# Mechanical.net
KiCad netlist of a schematic drawn in Altium Designer
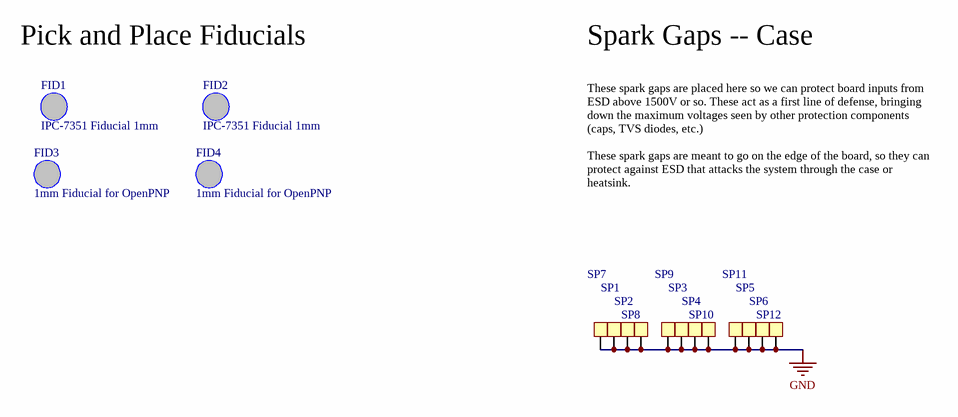
[diagram p0: Mechanical.SchDoc]

(export (version "E")
  (design (tool "Eeschema 10.0.6"))
  (components
    (comp (ref "FID1")
      (value "IPC-7351 Fiducial 1mm")
      (footprint "FIDUCIAL_1.5")
      (libsource (lib "Mechanical") (part "FIDUCIAL_1.5"))
    )
    (comp (ref "FID2")
      (value "IPC-7351 Fiducial 1mm")
      (footprint "FIDUCIAL_1.5")
      (libsource (lib "Mechanical") (part "FIDUCIAL_1.5"))
    )
    (comp (ref "FID3")
      (value "1mm Fiducial for OpenPNP")
      (footprint "FIDUCIAL-NEW")
      (libsource (lib "Mechanical") (part "FIDUCIAL_NEW"))
    )
    (comp (ref "FID4")
      (value "1mm Fiducial for OpenPNP")
      (footprint "FIDUCIAL-NEW")
      (libsource (lib "Mechanical") (part "FIDUCIAL_NEW"))
    )
    (comp (ref "SP1")
      (value "Spark Gap")
      (footprint "SparkGap")
      (description "Open square pad for spark gapping")
      (libsource (lib "PCBFeatures") (part "Spark Gap"))
    )
    (comp (ref "SP2")
      (value "Spark Gap")
      (footprint "SparkGap")
      (description "Open square pad for spark gapping")
      (libsource (lib "PCBFeatures") (part "Spark Gap"))
    )
    (comp (ref "SP3")
      (value "Spark Gap")
      (footprint "SparkGap")
      (description "Open square pad for spark gapping")
      (libsource (lib "PCBFeatures") (part "Spark Gap"))
    )
    (comp (ref "SP4")
      (value "Spark Gap")
      (footprint "SparkGap")
      (description "Open square pad for spark gapping")
      (libsource (lib "PCBFeatures") (part "Spark Gap"))
    )
    (comp (ref "SP5")
      (value "Spark Gap")
      (footprint "SparkGap")
      (description "Open square pad for spark gapping")
      (libsource (lib "PCBFeatures") (part "Spark Gap"))
    )
    (comp (ref "SP6")
      (value "Spark Gap")
      (footprint "SparkGap")
      (description "Open square pad for spark gapping")
      (libsource (lib "PCBFeatures") (part "Spark Gap"))
    )
    (comp (ref "SP7")
      (value "Spark Gap")
      (footprint "SparkGap")
      (description "Open square pad for spark gapping")
      (libsource (lib "PCBFeatures") (part "Spark Gap"))
    )
    (comp (ref "SP8")
      (value "Spark Gap")
      (footprint "SparkGap")
      (description "Open square pad for spark gapping")
      (libsource (lib "PCBFeatures") (part "Spark Gap"))
    )
    (comp (ref "SP9")
      (value "Spark Gap")
      (footprint "SparkGap")
      (description "Open square pad for spark gapping")
      (libsource (lib "PCBFeatures") (part "Spark Gap"))
    )
    (comp (ref "SP10")
      (value "Spark Gap")
      (footprint "SparkGap")
      (description "Open square pad for spark gapping")
      (libsource (lib "PCBFeatures") (part "Spark Gap"))
    )
    (comp (ref "SP11")
      (value "Spark Gap")
      (footprint "SparkGap")
      (description "Open square pad for spark gapping")
      (libsource (lib "PCBFeatures") (part "Spark Gap"))
    )
    (comp (ref "SP12")
      (value "Spark Gap")
      (footprint "SparkGap")
      (description "Open square pad for spark gapping")
      (libsource (lib "PCBFeatures") (part "Spark Gap"))
    )
  )
  (nets
    (net (code "1") (name "GND") (class "Default")
      (node (ref "SP1") (pin "1") (pinfunction "1_1") (pintype "passive"))
      (node (ref "SP10") (pin "1") (pinfunction "1_1") (pintype "passive"))
      (node (ref "SP11") (pin "1") (pinfunction "1_1") (pintype "passive"))
      (node (ref "SP12") (pin "1") (pinfunction "1_1") (pintype "passive"))
      (node (ref "SP2") (pin "1") (pinfunction "1_1") (pintype "passive"))
      (node (ref "SP3") (pin "1") (pinfunction "1_1") (pintype "passive"))
      (node (ref "SP4") (pin "1") (pinfunction "1_1") (pintype "passive"))
      (node (ref "SP5") (pin "1") (pinfunction "1_1") (pintype "passive"))
      (node (ref "SP6") (pin "1") (pinfunction "1_1") (pintype "passive"))
      (node (ref "SP7") (pin "1") (pinfunction "1_1") (pintype "passive"))
      (node (ref "SP8") (pin "1") (pinfunction "1_1") (pintype "passive"))
      (node (ref "SP9") (pin "1") (pinfunction "1_1") (pintype "passive"))
    )
    (net (code "2") (name "unconnected-(FID1-Pad1)") (class "Default")
      (node (ref "FID1") (pin "1") (pinfunction "1_1") (pintype "passive"))
    )
    (net (code "3") (name "unconnected-(FID2-Pad1)") (class "Default")
      (node (ref "FID2") (pin "1") (pinfunction "1_1") (pintype "passive"))
    )
    (net (code "4") (name "unconnected-(FID3-Pad1)") (class "Default")
      (node (ref "FID3") (pin "1") (pinfunction "1_1") (pintype "passive"))
    )
    (net (code "5") (name "unconnected-(FID4-Pad1)") (class "Default")
      (node (ref "FID4") (pin "1") (pinfunction "1_1") (pintype "passive"))
    )
  )
)
